# 03_-Python_Camera_Interface.net
KiCad netlist of a schematic drawn in Altium Designer
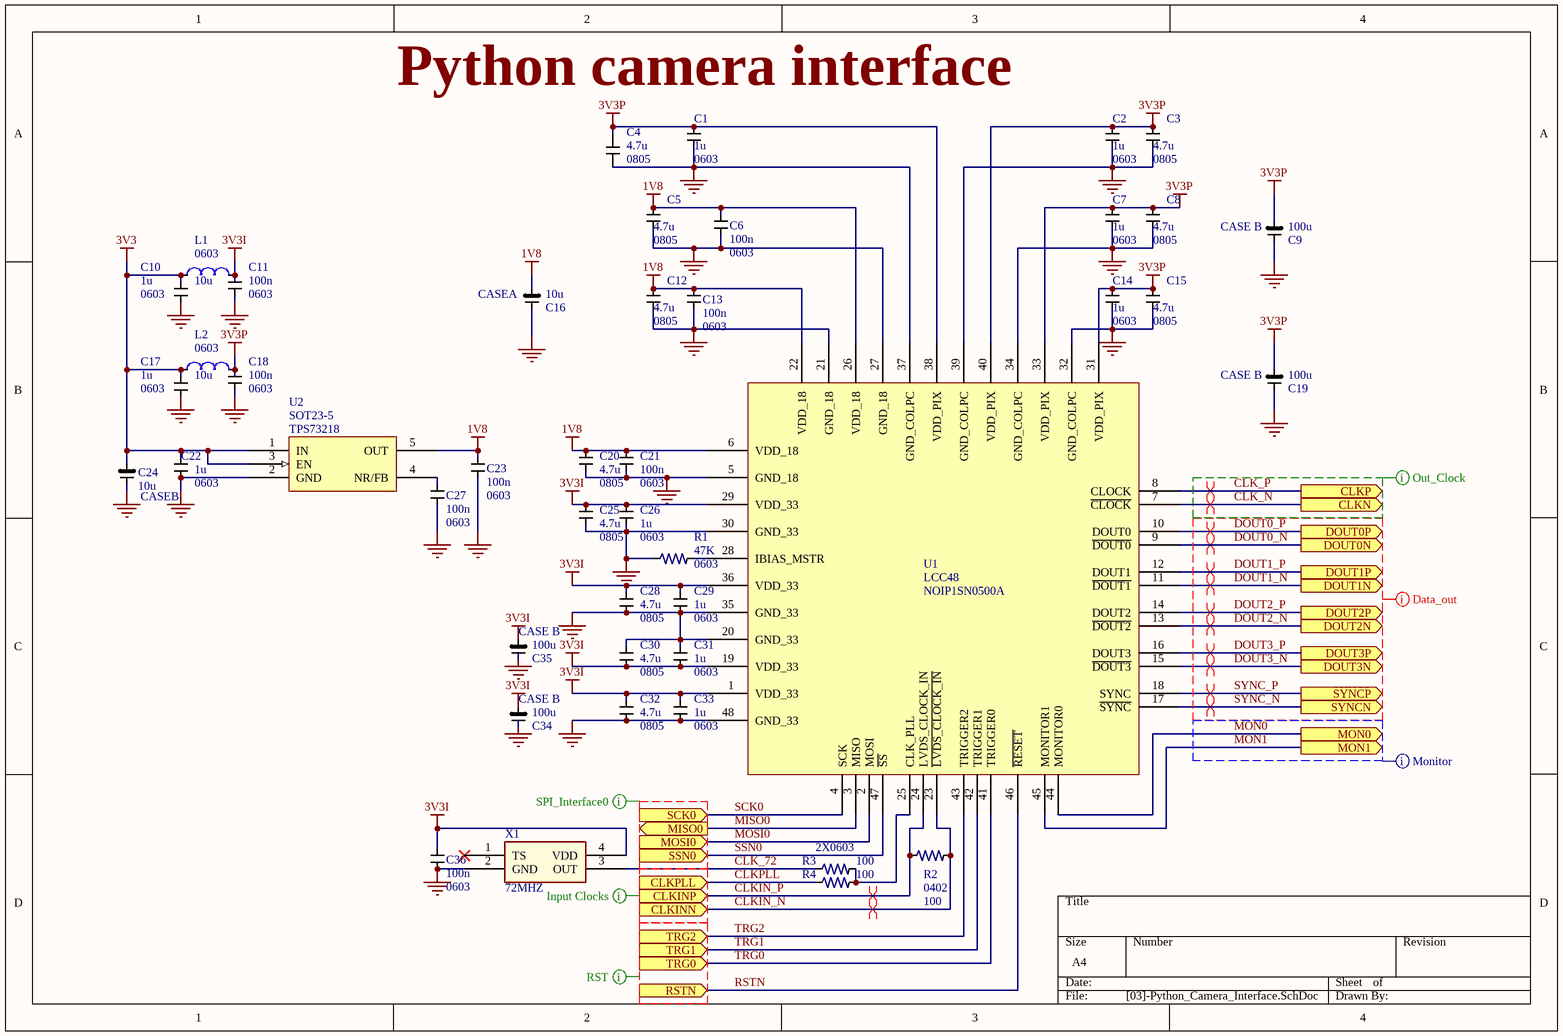
[diagram p0: [03]-Python_Camera_Interface.SchDoc]

(export (version "E")
  (design (tool "Eeschema 10.0.6"))
  (components
    (comp (ref "C1")
      (value "1u")
      (footprint "*0603")
      (fields (field (name "PCB LAYER:") "0603"))
      (libsource (lib "0603YC105KAT2A") (part "Component_1"))
    )
    (comp (ref "C2")
      (value "1u")
      (footprint "*0603")
      (fields (field (name "PCB LAYER:") "0603"))
      (libsource (lib "0603YC105KAT2A") (part "Component_1"))
    )
    (comp (ref "C3")
      (value "4.7u")
      (footprint "*CAPC2013X140N")
      (fields (field (name "PCB PACKAGE") "0805"))
      (libsource (lib "08053D475KAT2A") (part "Component_1"))
    )
    (comp (ref "C4")
      (value "4.7u")
      (footprint "*CAPC2013X140N")
      (fields (field (name "PCB PACKAGE") "0805"))
      (libsource (lib "") (part "Component_1_1"))
    )
    (comp (ref "C5")
      (value "4.7u")
      (footprint "*CAPC2013X140N")
      (fields (field (name "PCB PACKAGE") "0805"))
      (libsource (lib "08053D475KAT2A") (part "Component_1"))
    )
    (comp (ref "C6")
      (value "100n")
      (footprint "*CAPC1608X90N")
      (fields (field (name "PCB PACKAGE TYPE") "0603"))
      (libsource (lib "GRM188R71H104KA93D") (part "Component_1"))
    )
    (comp (ref "C7")
      (value "1u")
      (footprint "*0603")
      (fields (field (name "PCB LAYER:") "0603"))
      (libsource (lib "0603YC105KAT2A") (part "Component_1"))
    )
    (comp (ref "C8")
      (value "4.7u")
      (footprint "*CAPC2013X140N")
      (fields (field (name "PCB PACKAGE") "0805"))
      (libsource (lib "08053D475KAT2A") (part "Component_1"))
    )
    (comp (ref "C9")
      (value "100u")
      (footprint "CAPC3529X21N")
      (fields (field (name "CASE") "CASE B"))
      (libsource (lib "TAJB107K006TNJ") (part "Component_1"))
    )
    (comp (ref "C10")
      (value "1u")
      (fields (field (name "PCB SIZE") "0603"))
      (libsource (lib "0402ZD105KAT2A") (part "Component_1"))
    )
    (comp (ref "C11")
      (value "100n")
      (footprint "*CAPC1608X90N")
      (fields (field (name "PCB PACKAGE TYPE") "0603"))
      (libsource (lib "GRM188R71H104KA93D") (part "Component_1"))
    )
    (comp (ref "C12")
      (value "4.7u")
      (footprint "*CAPC2013X140N")
      (fields (field (name "PCB PACKAGE") "0805"))
      (libsource (lib "08053D475KAT2A") (part "Component_1"))
    )
    (comp (ref "C13")
      (value "100n")
      (footprint "*CAPC1608X90N")
      (fields (field (name "PCB PACKAGE TYPE") "0603"))
      (libsource (lib "GRM188R71H104KA93D") (part "Component_1"))
    )
    (comp (ref "C14")
      (value "1u")
      (footprint "*0603")
      (fields (field (name "PCB LAYER:") "0603"))
      (libsource (lib "0603YC105KAT2A") (part "Component_1"))
    )
    (comp (ref "C15")
      (value "4.7u")
      (footprint "*CAPC2013X140N")
      (fields (field (name "PCB PACKAGE") "0805"))
      (libsource (lib "08053D475KAT2A") (part "Component_1"))
    )
    (comp (ref "C16")
      (value "10u")
      (footprint "CAPCP3216X18N")
      (fields (field (name "CASE TYPE:") "CASEA"))
      (libsource (lib "T491A106M004AT") (part "Component_1"))
    )
    (comp (ref "C17")
      (value "1u")
      (fields (field (name "PCB SIZE") "0603"))
      (libsource (lib "0402ZD105KAT2A") (part "Component_1"))
    )
    (comp (ref "C18")
      (value "100n")
      (footprint "*CAPC1608X90N")
      (fields (field (name "PCB PACKAGE TYPE") "0603"))
      (libsource (lib "GRM188R71H104KA93D") (part "Component_1"))
    )
    (comp (ref "C19")
      (value "100u")
      (footprint "CAPC3529X21N")
      (fields (field (name "CASE") "CASE B"))
      (libsource (lib "TAJB107K006TNJ") (part "Component_1"))
    )
    (comp (ref "C20")
      (value "4.7u")
      (footprint "*CAPC2013X140N")
      (fields (field (name "PCB PACKAGE") "0805"))
      (libsource (lib "08053D475KAT2A") (part "Component_1"))
    )
    (comp (ref "C21")
      (value "100n")
      (footprint "*CAPC1608X90N")
      (fields (field (name "PCB PACKAGE TYPE") "0603"))
      (libsource (lib "GRM188R71H104KA93D") (part "Component_1"))
    )
    (comp (ref "C22")
      (value "1u")
      (footprint "*0603")
      (fields (field (name "PCB LAYER:") "0603"))
      (libsource (lib "0603YC105KAT2A") (part "Component_1"))
    )
    (comp (ref "C23")
      (value "100n")
      (footprint "*CAPC1608X90N")
      (fields (field (name "PCB PACKAGE TYPE") "0603"))
      (libsource (lib "GRM188R71H104KA93D") (part "Component_1"))
    )
    (comp (ref "C24")
      (value "10u")
      (footprint "CAPC3528X21N")
      (fields (field (name "PCB LAYER") "CASEB"))
      (libsource (lib "T495B106K010ATE600") (part "Component_1"))
    )
    (comp (ref "C25")
      (value "4.7u")
      (footprint "*CAPC2013X140N")
      (fields (field (name "PCB PACKAGE") "0805"))
      (libsource (lib "08053D475KAT2A") (part "Component_1"))
    )
    (comp (ref "C26")
      (value "1u")
      (footprint "*0603")
      (fields (field (name "PCB LAYER:") "0603"))
      (libsource (lib "0603YC105KAT2A") (part "Component_1"))
    )
    (comp (ref "C27")
      (value "100n")
      (footprint "*CAPC1608X90N")
      (fields (field (name "PCB PACKAGE TYPE") "0603"))
      (libsource (lib "GRM188R71H104KA93D") (part "Component_1"))
    )
    (comp (ref "C28")
      (value "4.7u")
      (footprint "*CAPC2013X140N")
      (fields (field (name "PCB PACKAGE") "0805"))
      (libsource (lib "08053D475KAT2A") (part "Component_1"))
    )
    (comp (ref "C29")
      (value "1u")
      (footprint "*0603")
      (fields (field (name "PCB LAYER:") "0603"))
      (libsource (lib "0603YC105KAT2A") (part "Component_1"))
    )
    (comp (ref "C30")
      (value "4.7u")
      (footprint "*CAPC2013X140N")
      (fields (field (name "PCB PACKAGE") "0805"))
      (libsource (lib "08053D475KAT2A") (part "Component_1"))
    )
    (comp (ref "C31")
      (value "1u")
      (footprint "*0603")
      (fields (field (name "PCB LAYER:") "0603"))
      (libsource (lib "0603YC105KAT2A") (part "Component_1"))
    )
    (comp (ref "C32")
      (value "4.7u")
      (footprint "*CAPC2013X140N")
      (fields (field (name "PCB PACKAGE") "0805"))
      (libsource (lib "08053D475KAT2A") (part "Component_1"))
    )
    (comp (ref "C33")
      (value "1u")
      (footprint "*0603")
      (fields (field (name "PCB LAYER:") "0603"))
      (libsource (lib "0603YC105KAT2A") (part "Component_1"))
    )
    (comp (ref "C34")
      (value "100u")
      (footprint "CAPC3529X21N")
      (fields (field (name "CASE") "CASE B"))
      (libsource (lib "TAJB107K006TNJ") (part "Component_1"))
    )
    (comp (ref "C35")
      (value "100u")
      (footprint "CAPC3529X21N")
      (fields (field (name "CASE") "CASE B"))
      (libsource (lib "TAJB107K006TNJ") (part "Component_1"))
    )
    (comp (ref "C36")
      (value "100n")
      (footprint "*CAPC1608X90N")
      (fields (field (name "PCB PACKAGE TYPE") "0603"))
      (libsource (lib "GRM188R71H104KA93D") (part "Component_1"))
    )
    (comp (ref "L1")
      (value "10u")
      (footprint "*INDC1608X95N")
      (fields (field (name "PCB LAYOUT:") "0603"))
      (libsource (lib "MLZ1608M100WTD25") (part "Component_1"))
    )
    (comp (ref "L2")
      (value "10u")
      (footprint "*INDC1608X95N")
      (fields (field (name "PCB LAYOUT:") "0603"))
      (libsource (lib "MLZ1608M100WTD25") (part "Component_1"))
    )
    (comp (ref "R1")
      (value "47K")
      (footprint "*0603")
      (description "Res Thin Film 0603 76.8 Ohm 0.1% 1/10W Â±15ppm/Â°C Molded SMD Paper T/R")
      (fields
        (field (name "MP") "RP73D1J76R8BTDG")
        (field (name "MF") "TE Connectivity / Holsworthy")
        (field (name "FOOT PRINT") "0603")
      )
      (libsource (lib "CRCW060347K0FKEA") (part "RP73D1J76R8BTDG"))
    )
    (comp (ref "R2")
      (value "100")
      (footprint "*R0402")
      (description "Res Thin Film 0603 76.8 Ohm 0.1% 1/10W Â±15ppm/Â°C Molded SMD Paper T/R")
      (fields (field (name "PCB FOOTPRINT") "0402"))
      (libsource (lib "SMD-RES-100K-1_-1_16W_0402_") (part "RP73D1J76R8BTDG"))
    )
    (comp (ref "R3")
      (value "100")
      (footprint "*0603")
      (description "Res Thin Film 0603 76.8 Ohm 0.1% 1/10W Â±15ppm/Â°C Molded SMD Paper T/R")
      (fields
        (field (name "MP") "RP73D1J76R8BTDG")
        (field (name "MF") "TE Connectivity / Holsworthy")
        (field (name "FOOT PRINT") "2X0603")
      )
      (libsource (lib "CRCW060347K0FKEA") (part "RP73D1J76R8BTDG"))
    )
    (comp (ref "R4")
      (value "100")
      (footprint "*0603")
      (description "Res Thin Film 0603 76.8 Ohm 0.1% 1/10W Â±15ppm/Â°C Molded SMD Paper T/R")
      (fields (field (name "MP") "RP73D1J76R8BTDG") (field (name "MF") "TE Connectivity / Holsworthy"))
      (libsource (lib "CRCW060347K0FKEA") (part "RP73D1J76R8BTDG"))
    )
    (comp (ref "U1")
      (value "NOIP1SN0500A")
      (footprint "LCC101P1430X1430X228-48N")
      (description "Python camera sensor. Having pixel output of 500 by 600.")
      (fields
        (field (name "PART NO.") "NOIP1SN0500A-QDI")
        (field (name "PACKAGE TYPE") "LCC48")
        (field (name "DESIGNER") "Faheem")
      )
      (libsource (lib "NOIP1SN0500A") (part "Component_1"))
    )
    (comp (ref "U2")
      (value "TPS73218")
      (footprint "*SOT95P280X145-5N")
      (fields (field (name "PCB FOOTPRINT TYPE:") "SOT23-5"))
      (libsource (lib "TPS73218DBVT") (part "Component_1"))
    )
    (comp (ref "X1")
      (value "72MHZ")
      (footprint "OSCSC320X250X100N")
      (fields (field (name "MF_PART NO.") "ASFLMB-72.000MHZ-XY-T"))
      (libsource (lib "ASFLMB-72.000MHZ-XY-T") (part "Component_1"))
    )
  )
  (nets
    (net (code "1") (name "/CLKIN_N") (class "Default")
      (node (ref "R2") (pin "2") (pinfunction "2_2") (pintype "passive"))
      (node (ref "U1") (pin "23") (pinfunction "~{LVDS_CLOCK_IN}_23") (pintype "passive"))
    )
    (net (code "2") (name "/CLKIN_P") (class "Default")
      (node (ref "R2") (pin "1") (pinfunction "1_1") (pintype "passive"))
      (node (ref "U1") (pin "24") (pinfunction "LVDS_CLOCK_IN_24") (pintype "passive"))
    )
    (net (code "3") (name "/CLKPLL") (class "Default")
      (node (ref "R4") (pin "1") (pinfunction "1_1") (pintype "passive"))
    )
    (net (code "4") (name "/CLK_72") (class "Default")
      (node (ref "R3") (pin "1") (pinfunction "1_1") (pintype "passive"))
      (node (ref "X1") (pin "3") (pinfunction "OUT_3") (pintype "passive"))
    )
    (net (code "5") (name "/CLK_N") (class "Default")
      (node (ref "U1") (pin "7") (pinfunction "~{CLOCK}_7") (pintype "passive"))
    )
    (net (code "6") (name "/CLK_P") (class "Default")
      (node (ref "U1") (pin "8") (pinfunction "CLOCK_8") (pintype "passive"))
    )
    (net (code "7") (name "/DOUT0_N") (class "Default")
      (node (ref "U1") (pin "9") (pinfunction "~{DOUT0}_9") (pintype "passive"))
    )
    (net (code "8") (name "/DOUT0_P") (class "Default")
      (node (ref "U1") (pin "10") (pinfunction "DOUT0_10") (pintype "passive"))
    )
    (net (code "9") (name "/DOUT1_N") (class "Default")
      (node (ref "U1") (pin "11") (pinfunction "~{DOUT1}_11") (pintype "passive"))
    )
    (net (code "10") (name "/DOUT1_P") (class "Default")
      (node (ref "U1") (pin "12") (pinfunction "DOUT1_12") (pintype "passive"))
    )
    (net (code "11") (name "/DOUT2_N") (class "Default")
      (node (ref "U1") (pin "13") (pinfunction "~{DOUT2}_13") (pintype "passive"))
    )
    (net (code "12") (name "/DOUT2_P") (class "Default")
      (node (ref "U1") (pin "14") (pinfunction "DOUT2_14") (pintype "passive"))
    )
    (net (code "13") (name "/DOUT3_N") (class "Default")
      (node (ref "U1") (pin "15") (pinfunction "~{DOUT3}_15") (pintype "passive"))
    )
    (net (code "14") (name "/DOUT3_P") (class "Default")
      (node (ref "U1") (pin "16") (pinfunction "DOUT3_16") (pintype "passive"))
    )
    (net (code "15") (name "/MISO0") (class "Default")
      (node (ref "U1") (pin "3") (pinfunction "MISO_3") (pintype "passive"))
    )
    (net (code "16") (name "/MON0") (class "Default")
      (node (ref "U1") (pin "44") (pinfunction "MONITOR0_44") (pintype "passive"))
    )
    (net (code "17") (name "/MON1") (class "Default")
      (node (ref "U1") (pin "45") (pinfunction "MONITOR1_45") (pintype "passive"))
    )
    (net (code "18") (name "/MOSI0") (class "Default")
      (node (ref "U1") (pin "2") (pinfunction "MOSI_2") (pintype "passive"))
    )
    (net (code "19") (name "/RSTN") (class "Default")
      (node (ref "U1") (pin "46") (pinfunction "~{RESET}_46") (pintype "passive"))
    )
    (net (code "20") (name "/SCK0") (class "Default")
      (node (ref "U1") (pin "4") (pinfunction "SCK_4") (pintype "passive"))
    )
    (net (code "21") (name "/SSN0") (class "Default")
      (node (ref "U1") (pin "47") (pinfunction "~{SS}_47") (pintype "passive"))
    )
    (net (code "22") (name "/SYNC_N") (class "Default")
      (node (ref "U1") (pin "17") (pinfunction "~{SYNC}_17") (pintype "passive"))
    )
    (net (code "23") (name "/SYNC_P") (class "Default")
      (node (ref "U1") (pin "18") (pinfunction "SYNC_18") (pintype "passive"))
    )
    (net (code "24") (name "/TRG0") (class "Default")
      (node (ref "U1") (pin "41") (pinfunction "TRIGGER0_41") (pintype "passive"))
    )
    (net (code "25") (name "/TRG1") (class "Default")
      (node (ref "U1") (pin "42") (pinfunction "TRIGGER1_42") (pintype "passive"))
    )
    (net (code "26") (name "/TRG2") (class "Default")
      (node (ref "U1") (pin "43") (pinfunction "TRIGGER2_43") (pintype "passive"))
    )
    (net (code "27") (name "1V8") (class "Default")
      (node (ref "C12") (pin "2") (pinfunction "2_2") (pintype "passive"))
      (node (ref "C13") (pin "2") (pinfunction "2_2") (pintype "passive"))
      (node (ref "C16") (pin "1") (pinfunction "1_1") (pintype "passive"))
      (node (ref "C20") (pin "2") (pinfunction "2_2") (pintype "passive"))
      (node (ref "C21") (pin "2") (pinfunction "2_2") (pintype "passive"))
      (node (ref "C23") (pin "2") (pinfunction "2_2") (pintype "passive"))
      (node (ref "C5") (pin "2") (pinfunction "2_2") (pintype "passive"))
      (node (ref "C6") (pin "2") (pinfunction "2_2") (pintype "passive"))
      (node (ref "U1") (pin "22") (pinfunction "VDD_18_22") (pintype "power_in"))
      (node (ref "U1") (pin "26") (pinfunction "VDD_18_26") (pintype "power_in"))
      (node (ref "U1") (pin "6") (pinfunction "VDD_18_6") (pintype "power_in"))
      (node (ref "U2") (pin "5") (pinfunction "OUT_5") (pintype "power_in"))
    )
    (net (code "28") (name "3V3") (class "Default")
      (node (ref "C10") (pin "2") (pinfunction "2_2") (pintype "passive"))
      (node (ref "C17") (pin "2") (pinfunction "2_2") (pintype "passive"))
      (node (ref "C22") (pin "2") (pinfunction "2_2") (pintype "passive"))
      (node (ref "C24") (pin "1") (pinfunction "1_1") (pintype "passive"))
      (node (ref "L1") (pin "1") (pinfunction "1_1") (pintype "passive"))
      (node (ref "L2") (pin "1") (pinfunction "1_1") (pintype "passive"))
      (node (ref "U2") (pin "1") (pinfunction "IN_1") (pintype "power_in"))
      (node (ref "U2") (pin "3") (pinfunction "EN_3") (pintype "input"))
    )
    (net (code "29") (name "3V3I") (class "Default")
      (node (ref "C11") (pin "2") (pinfunction "2_2") (pintype "passive"))
      (node (ref "C25") (pin "2") (pinfunction "2_2") (pintype "passive"))
      (node (ref "C26") (pin "2") (pinfunction "2_2") (pintype "passive"))
      (node (ref "C28") (pin "2") (pinfunction "2_2") (pintype "passive"))
      (node (ref "C29") (pin "2") (pinfunction "2_2") (pintype "passive"))
      (node (ref "C30") (pin "1") (pinfunction "1_1") (pintype "passive"))
      (node (ref "C31") (pin "1") (pinfunction "1_1") (pintype "passive"))
      (node (ref "C32") (pin "2") (pinfunction "2_2") (pintype "passive"))
      (node (ref "C33") (pin "2") (pinfunction "2_2") (pintype "passive"))
      (node (ref "C34") (pin "1") (pinfunction "1_1") (pintype "passive"))
      (node (ref "C35") (pin "1") (pinfunction "1_1") (pintype "passive"))
      (node (ref "C36") (pin "2") (pinfunction "2_2") (pintype "passive"))
      (node (ref "L1") (pin "2") (pinfunction "2_2") (pintype "passive"))
      (node (ref "U1") (pin "1") (pinfunction "VDD_33_1") (pintype "power_in"))
      (node (ref "U1") (pin "19") (pinfunction "VDD_33_19") (pintype "power_in"))
      (node (ref "U1") (pin "29") (pinfunction "VDD_33_29") (pintype "power_in"))
      (node (ref "U1") (pin "36") (pinfunction "VDD_33_36") (pintype "power_in"))
      (node (ref "X1") (pin "4") (pinfunction "VDD_4") (pintype "passive"))
    )
    (net (code "30") (name "3V3P") (class "Default")
      (node (ref "C1") (pin "2") (pinfunction "2_2") (pintype "passive"))
      (node (ref "C14") (pin "2") (pinfunction "2_2") (pintype "passive"))
      (node (ref "C15") (pin "2") (pinfunction "2_2") (pintype "passive"))
      (node (ref "C18") (pin "2") (pinfunction "2_2") (pintype "passive"))
      (node (ref "C19") (pin "1") (pinfunction "1_1") (pintype "passive"))
      (node (ref "C2") (pin "2") (pinfunction "2_2") (pintype "passive"))
      (node (ref "C3") (pin "2") (pinfunction "2_2") (pintype "passive"))
      (node (ref "C4") (pin "1") (pinfunction "1_1") (pintype "passive"))
      (node (ref "C7") (pin "2") (pinfunction "2_2") (pintype "passive"))
      (node (ref "C8") (pin "2") (pinfunction "2_2") (pintype "passive"))
      (node (ref "C9") (pin "1") (pinfunction "1_1") (pintype "passive"))
      (node (ref "L2") (pin "2") (pinfunction "2_2") (pintype "passive"))
      (node (ref "U1") (pin "31") (pinfunction "VDD_PIX_31") (pintype "power_in"))
      (node (ref "U1") (pin "33") (pinfunction "VDD_PIX_33") (pintype "power_in"))
      (node (ref "U1") (pin "38") (pinfunction "VDD_PIX_38") (pintype "power_in"))
      (node (ref "U1") (pin "40") (pinfunction "VDD_PIX_40") (pintype "power_in"))
    )
    (net (code "31") (name "GND") (class "Default")
      (node (ref "C1") (pin "1") (pinfunction "1_1") (pintype "passive"))
      (node (ref "C10") (pin "1") (pinfunction "1_1") (pintype "passive"))
      (node (ref "C11") (pin "1") (pinfunction "1_1") (pintype "passive"))
      (node (ref "C12") (pin "1") (pinfunction "1_1") (pintype "passive"))
      (node (ref "C13") (pin "1") (pinfunction "1_1") (pintype "passive"))
      (node (ref "C14") (pin "1") (pinfunction "1_1") (pintype "passive"))
      (node (ref "C15") (pin "1") (pinfunction "1_1") (pintype "passive"))
      (node (ref "C16") (pin "2") (pinfunction "2_2") (pintype "passive"))
      (node (ref "C17") (pin "1") (pinfunction "1_1") (pintype "passive"))
      (node (ref "C18") (pin "1") (pinfunction "1_1") (pintype "passive"))
      (node (ref "C19") (pin "2") (pinfunction "2_2") (pintype "passive"))
      (node (ref "C2") (pin "1") (pinfunction "1_1") (pintype "passive"))
      (node (ref "C20") (pin "1") (pinfunction "1_1") (pintype "passive"))
      (node (ref "C21") (pin "1") (pinfunction "1_1") (pintype "passive"))
      (node (ref "C22") (pin "1") (pinfunction "1_1") (pintype "passive"))
      (node (ref "C23") (pin "1") (pinfunction "1_1") (pintype "passive"))
      (node (ref "C24") (pin "2") (pinfunction "2_2") (pintype "passive"))
      (node (ref "C25") (pin "1") (pinfunction "1_1") (pintype "passive"))
      (node (ref "C26") (pin "1") (pinfunction "1_1") (pintype "passive"))
      (node (ref "C27") (pin "1") (pinfunction "1_1") (pintype "passive"))
      (node (ref "C28") (pin "1") (pinfunction "1_1") (pintype "passive"))
      (node (ref "C29") (pin "1") (pinfunction "1_1") (pintype "passive"))
      (node (ref "C3") (pin "1") (pinfunction "1_1") (pintype "passive"))
      (node (ref "C30") (pin "2") (pinfunction "2_2") (pintype "passive"))
      (node (ref "C31") (pin "2") (pinfunction "2_2") (pintype "passive"))
      (node (ref "C32") (pin "1") (pinfunction "1_1") (pintype "passive"))
      (node (ref "C33") (pin "1") (pinfunction "1_1") (pintype "passive"))
      (node (ref "C34") (pin "2") (pinfunction "2_2") (pintype "passive"))
      (node (ref "C35") (pin "2") (pinfunction "2_2") (pintype "passive"))
      (node (ref "C36") (pin "1") (pinfunction "1_1") (pintype "passive"))
      (node (ref "C4") (pin "2") (pinfunction "2_2") (pintype "passive"))
      (node (ref "C5") (pin "1") (pinfunction "1_1") (pintype "passive"))
      (node (ref "C6") (pin "1") (pinfunction "1_1") (pintype "passive"))
      (node (ref "C7") (pin "1") (pinfunction "1_1") (pintype "passive"))
      (node (ref "C8") (pin "1") (pinfunction "1_1") (pintype "passive"))
      (node (ref "C9") (pin "2") (pinfunction "2_2") (pintype "passive"))
      (node (ref "R1") (pin "1") (pinfunction "1_1") (pintype "passive"))
      (node (ref "U1") (pin "20") (pinfunction "GND_33_20") (pintype "power_in"))
      (node (ref "U1") (pin "21") (pinfunction "GND_18_21") (pintype "power_in"))
      (node (ref "U1") (pin "27") (pinfunction "GND_18_27") (pintype "power_in"))
      (node (ref "U1") (pin "30") (pinfunction "GND_33_30") (pintype "power_in"))
      (node (ref "U1") (pin "32") (pinfunction "GND_COLPC_32") (pintype "power_in"))
      (node (ref "U1") (pin "34") (pinfunction "GND_COLPC_34") (pintype "power_in"))
      (node (ref "U1") (pin "35") (pinfunction "GND_33_35") (pintype "power_in"))
      (node (ref "U1") (pin "37") (pinfunction "GND_COLPC_37") (pintype "power_in"))
      (node (ref "U1") (pin "39") (pinfunction "GND_COLPC_39") (pintype "power_in"))
      (node (ref "U1") (pin "48") (pinfunction "GND_33_48") (pintype "power_in"))
      (node (ref "U1") (pin "5") (pinfunction "GND_18_5") (pintype "power_in"))
      (node (ref "U2") (pin "2") (pinfunction "GND_2") (pintype "power_in"))
      (node (ref "X1") (pin "2") (pinfunction "GND_2") (pintype "passive"))
    )
    (net (code "32") (name "Net-(U1-CLK_PLL)") (class "Default")
      (node (ref "R3") (pin "2") (pinfunction "2_2") (pintype "passive"))
      (node (ref "R4") (pin "2") (pinfunction "2_2") (pintype "passive"))
      (node (ref "U1") (pin "25") (pinfunction "CLK_PLL_25") (pintype "passive"))
    )
    (net (code "33") (name "Net-(U1-IBIAS_MSTR)") (class "Default")
      (node (ref "R1") (pin "2") (pinfunction "2_2") (pintype "passive"))
      (node (ref "U1") (pin "28") (pinfunction "IBIAS_MSTR_28") (pintype "passive"))
    )
    (net (code "34") (name "Net-(U2-NR{slash}FB)") (class "Default")
      (node (ref "C27") (pin "2") (pinfunction "2_2") (pintype "passive"))
      (node (ref "U2") (pin "4") (pinfunction "NR/FB_4") (pintype "open_emitter"))
    )
    (net (code "35") (name "unconnected-(X1-TS-Pad1)") (class "Default")
      (node (ref "X1") (pin "1") (pinfunction "TS_1") (pintype "passive+no_connect"))
    )
  )
)
